# ETH_PCIE_CTRL.net
KiCad netlist of a schematic drawn in Altium Designer
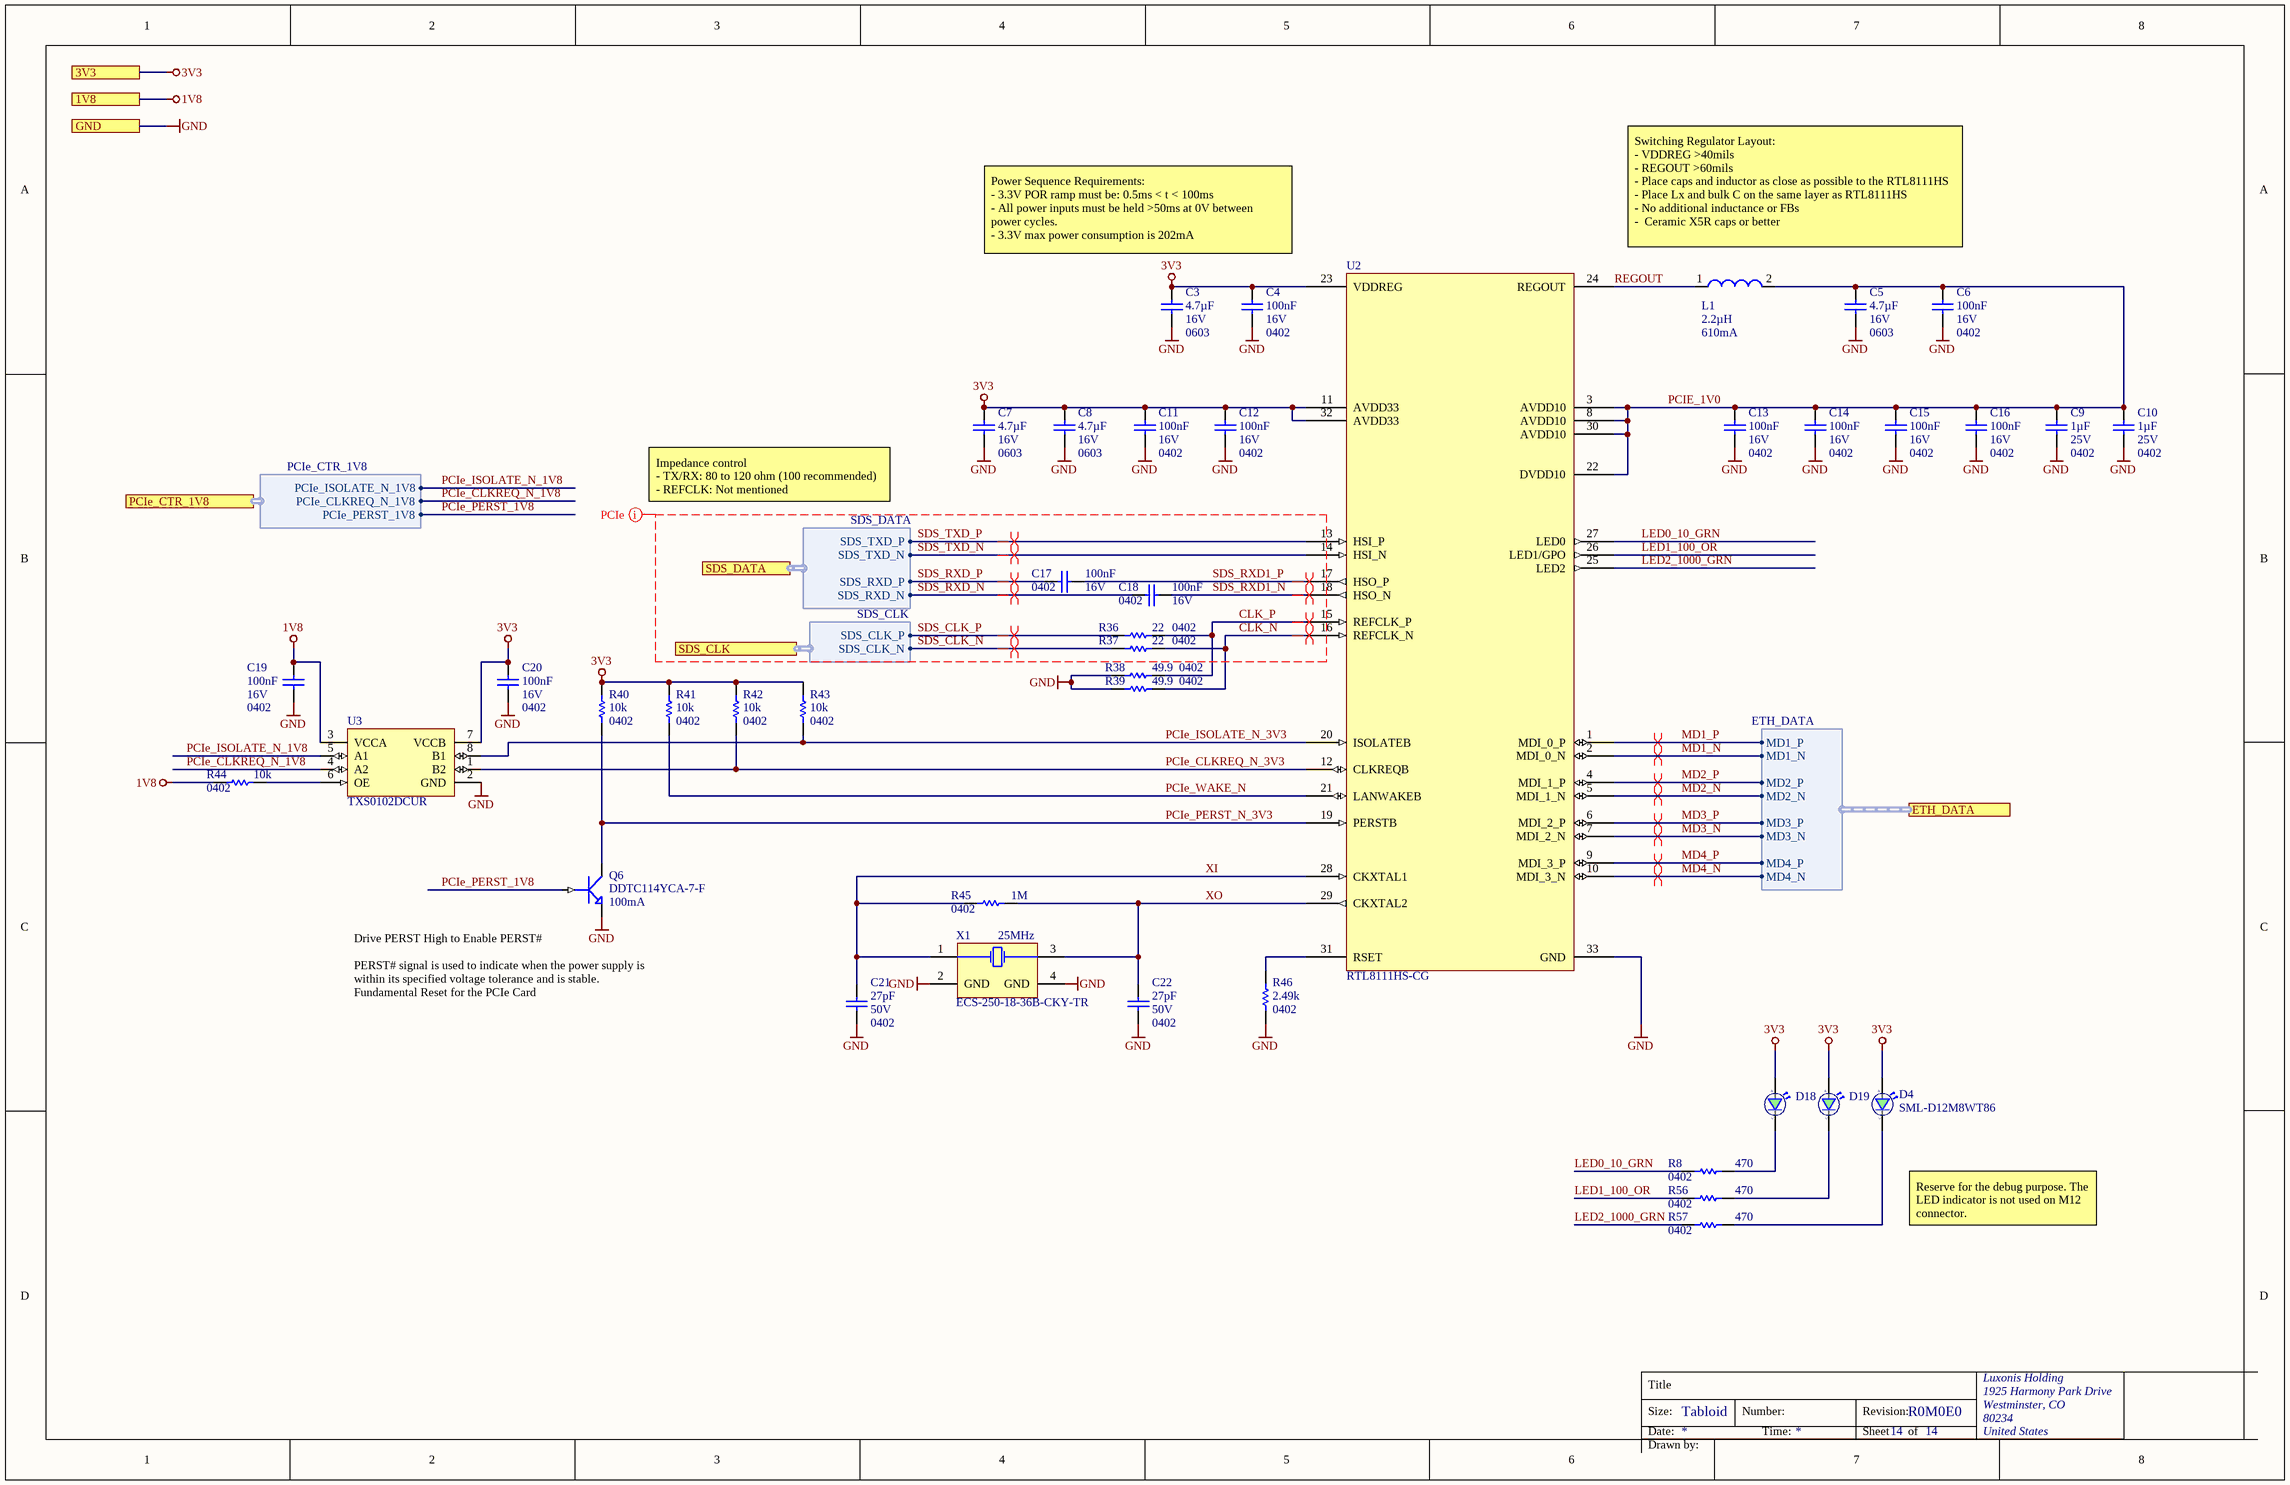
[diagram p0: ETH_PCIE_CTRL.SchDoc]

(export (version "E")
  (design (tool "Eeschema 10.0.6"))
  (components
    (comp (ref "C3")
      (value "4.7µF")
      (footprint "CAPC0603(1608)100_N")
      (description "CAP CER 4.7UF 16V X5R 0603 10%")
      (fields
        (field (name "VOLTAGE RATING") "16V")
        (field (name "CASE/PACKAGE") "0603")
        (field (name "TOLERANCE") "10%")
        (field (name "Comment") "GRM188R61C475KAAJD")
      )
      (libsource (lib "Luxonis LLC") (part "LLL153C70G474ME17E"))
    )
    (comp (ref "C4")
      (value "100nF")
      (footprint "CAPC0402(1005)60_N")
      (description "CAP CER 0.1UF 16V X7R 0402 10%")
      (fields
        (field (name "VOLTAGE RATING") "16V")
        (field (name "CASE/PACKAGE") "0402")
        (field (name "TOLERANCE") "10%")
        (field (name "Comment") "CL05B104KO5NFNC")
      )
      (libsource (lib "Luxonis LLC") (part "GRM188R61C475KAAJD"))
    )
    (comp (ref "C5")
      (value "4.7µF")
      (footprint "CAPC0603(1608)100_N")
      (description "CAP CER 4.7UF 16V X5R 0603 10%")
      (fields
        (field (name "VOLTAGE RATING") "16V")
        (field (name "CASE/PACKAGE") "0603")
        (field (name "TOLERANCE") "10%")
        (field (name "Comment") "GRM188R61C475KAAJD")
      )
      (libsource (lib "Luxonis LLC") (part "LLL153C70G474ME17E"))
    )
    (comp (ref "C6")
      (value "100nF")
      (footprint "CAPC0402(1005)60_N")
      (description "CAP CER 0.1UF 16V X7R 0402 10%")
      (fields
        (field (name "VOLTAGE RATING") "16V")
        (field (name "CASE/PACKAGE") "0402")
        (field (name "TOLERANCE") "10%")
        (field (name "Comment") "CL05B104KO5NFNC")
      )
      (libsource (lib "Luxonis LLC") (part "GRM188R61C475KAAJD"))
    )
    (comp (ref "C7")
      (value "4.7µF")
      (footprint "CAPC0603(1608)100_N")
      (description "CAP CER 4.7UF 16V X5R 0603 10%")
      (fields
        (field (name "VOLTAGE RATING") "16V")
        (field (name "CASE/PACKAGE") "0603")
        (field (name "TOLERANCE") "10%")
        (field (name "Comment") "GRM188R61C475KAAJD")
      )
      (libsource (lib "Luxonis LLC") (part "LLL153C70G474ME17E"))
    )
    (comp (ref "C8")
      (value "4.7µF")
      (footprint "CAPC0603(1608)100_N")
      (description "CAP CER 4.7UF 16V X5R 0603 10%")
      (fields
        (field (name "VOLTAGE RATING") "16V")
        (field (name "CASE/PACKAGE") "0603")
        (field (name "TOLERANCE") "10%")
        (field (name "Comment") "GRM188R61C475KAAJD")
      )
      (libsource (lib "Luxonis LLC") (part "LLL153C70G474ME17E"))
    )
    (comp (ref "C9")
      (value "1µF")
      (footprint "CAPC0402(1005)70_N")
      (description "CAP CER 1UF 25V X5R 0402 10%")
      (fields
        (field (name "VOLTAGE RATING") "25V")
        (field (name "CASE/PACKAGE") "0402")
        (field (name "TOLERANCE") "10%")
        (field (name "Comment") "GRM155R61E105KA12D")
      )
      (libsource (lib "Luxonis LLC") (part "GRM188R61C475KAAJD"))
    )
    (comp (ref "C10")
      (value "1µF")
      (footprint "CAPC0402(1005)70_N")
      (description "CAP CER 1UF 25V X5R 0402 10%")
      (fields
        (field (name "VOLTAGE RATING") "25V")
        (field (name "CASE/PACKAGE") "0402")
        (field (name "TOLERANCE") "10%")
        (field (name "Comment") "GRM155R61E105KA12D")
      )
      (libsource (lib "Luxonis LLC") (part "GRM188R61C475KAAJD"))
    )
    (comp (ref "C11")
      (value "100nF")
      (footprint "CAPC0402(1005)60_N")
      (description "CAP CER 0.1UF 16V X7R 0402 10%")
      (fields
        (field (name "VOLTAGE RATING") "16V")
        (field (name "CASE/PACKAGE") "0402")
        (field (name "TOLERANCE") "10%")
        (field (name "Comment") "CL05B104KO5NFNC")
      )
      (libsource (lib "Luxonis LLC") (part "GRM188R61C475KAAJD"))
    )
    (comp (ref "C12")
      (value "100nF")
      (footprint "CAPC0402(1005)60_N")
      (description "CAP CER 0.1UF 16V X7R 0402 10%")
      (fields
        (field (name "VOLTAGE RATING") "16V")
        (field (name "CASE/PACKAGE") "0402")
        (field (name "TOLERANCE") "10%")
        (field (name "Comment") "CL05B104KO5NFNC")
      )
      (libsource (lib "Luxonis LLC") (part "GRM188R61C475KAAJD"))
    )
    (comp (ref "C13")
      (value "100nF")
      (footprint "CAPC0402(1005)60_N")
      (description "CAP CER 0.1UF 16V X7R 0402 10%")
      (fields
        (field (name "VOLTAGE RATING") "16V")
        (field (name "CASE/PACKAGE") "0402")
        (field (name "TOLERANCE") "10%")
        (field (name "Comment") "CL05B104KO5NFNC")
      )
      (libsource (lib "Luxonis LLC") (part "GRM188R61C475KAAJD"))
    )
    (comp (ref "C14")
      (value "100nF")
      (footprint "CAPC0402(1005)60_N")
      (description "CAP CER 0.1UF 16V X7R 0402 10%")
      (fields
        (field (name "VOLTAGE RATING") "16V")
        (field (name "CASE/PACKAGE") "0402")
        (field (name "TOLERANCE") "10%")
        (field (name "Comment") "CL05B104KO5NFNC")
      )
      (libsource (lib "Luxonis LLC") (part "GRM188R61C475KAAJD"))
    )
    (comp (ref "C15")
      (value "100nF")
      (footprint "CAPC0402(1005)60_N")
      (description "CAP CER 0.1UF 16V X7R 0402 10%")
      (fields
        (field (name "VOLTAGE RATING") "16V")
        (field (name "CASE/PACKAGE") "0402")
        (field (name "TOLERANCE") "10%")
        (field (name "Comment") "CL05B104KO5NFNC")
      )
      (libsource (lib "Luxonis LLC") (part "GRM188R61C475KAAJD"))
    )
    (comp (ref "C16")
      (value "100nF")
      (footprint "CAPC0402(1005)60_N")
      (description "CAP CER 0.1UF 16V X7R 0402 10%")
      (fields
        (field (name "VOLTAGE RATING") "16V")
        (field (name "CASE/PACKAGE") "0402")
        (field (name "TOLERANCE") "10%")
        (field (name "Comment") "CL05B104KO5NFNC")
      )
      (libsource (lib "Luxonis LLC") (part "GRM188R61C475KAAJD"))
    )
    (comp (ref "C17")
      (value "100nF")
      (footprint "CAPC0402(1005)60_N")
      (description "CAP CER 0.1UF 16V X7R 0402 10%")
      (fields
        (field (name "VOLTAGE RATING") "16V")
        (field (name "CASE/PACKAGE") "0402")
        (field (name "TOLERANCE") "10%")
        (field (name "Comment") "CL05B104KO5NFNC")
      )
      (libsource (lib "Luxonis LLC") (part "GRM188R61C475KAAJD"))
    )
    (comp (ref "C18")
      (value "100nF")
      (footprint "CAPC0402(1005)60_N")
      (description "CAP CER 0.1UF 16V X7R 0402 10%")
      (fields
        (field (name "VOLTAGE RATING") "16V")
        (field (name "CASE/PACKAGE") "0402")
        (field (name "TOLERANCE") "10%")
        (field (name "Comment") "CL05B104KO5NFNC")
      )
      (libsource (lib "Luxonis LLC") (part "GRM188R61C475KAAJD"))
    )
    (comp (ref "C19")
      (value "100nF")
      (footprint "CAPC0402(1005)60_N")
      (description "CAP CER 0.1UF 16V X7R 0402 10%")
      (fields
        (field (name "VOLTAGE RATING") "16V")
        (field (name "CASE/PACKAGE") "0402")
        (field (name "TOLERANCE") "10%")
        (field (name "Comment") "CL05B104KO5NFNC")
      )
      (libsource (lib "Luxonis LLC") (part "GRM188R61C475KAAJD"))
    )
    (comp (ref "C20")
      (value "100nF")
      (footprint "CAPC0402(1005)60_N")
      (description "CAP CER 0.1UF 16V X7R 0402 10%")
      (fields
        (field (name "VOLTAGE RATING") "16V")
        (field (name "CASE/PACKAGE") "0402")
        (field (name "TOLERANCE") "10%")
        (field (name "Comment") "CL05B104KO5NFNC")
      )
      (libsource (lib "Luxonis LLC") (part "GRM188R61C475KAAJD"))
    )
    (comp (ref "C21")
      (value "27pF")
      (footprint "CAPC0402(1005)60_N")
      (description "CAP CER 27PF 50V C0G 0402 5%")
      (fields
        (field (name "VOLTAGE RATING") "50V")
        (field (name "TOLERANCE") "5%")
        (field (name "CASE/PACKAGE") "0402")
        (field (name "Comment") "C0402C270J5GACTU")
      )
      (libsource (lib "Luxonis LLC") (part "GRM188R61C475KAAJD"))
    )
    (comp (ref "C22")
      (value "27pF")
      (footprint "CAPC0402(1005)60_N")
      (description "CAP CER 27PF 50V C0G 0402 5%")
      (fields
        (field (name "VOLTAGE RATING") "50V")
        (field (name "TOLERANCE") "5%")
        (field (name "CASE/PACKAGE") "0402")
        (field (name "Comment") "C0402C270J5GACTU")
      )
      (libsource (lib "Luxonis LLC") (part "GRM188R61C475KAAJD"))
    )
    (comp (ref "D4")
      (value "SML-D12M8WT86")
      (footprint "SML_D1xx8W")
      (description "LED GREEN DIFFUSED 0603 SMD Green 572nm LED Indication - Discrete 2.2V 0603 (1608 Metric)")
      (libsource (lib "Luxonis LLC") (part "SML-D12M8WT86"))
    )
    (comp (ref "D18")
      (value "SML-D12M8WT86")
      (footprint "SML_D1xx8W")
      (description "LED GREEN DIFFUSED 0603 SMD Green 572nm LED Indication - Discrete 2.2V 0603 (1608 Metric)")
      (libsource (lib "Luxonis LLC") (part "SML-D12M8WT86"))
    )
    (comp (ref "D19")
      (value "SML-D12M8WT86")
      (footprint "SML_D1xx8W")
      (description "LED GREEN DIFFUSED 0603 SMD Green 572nm LED Indication - Discrete 2.2V 0603 (1608 Metric)")
      (libsource (lib "Luxonis LLC") (part "SML-D12M8WT86"))
    )
    (comp (ref "L1")
      (value "2.2µH")
      (footprint "LQH32NH2R2J23L")
      (description "FIXED IND 2.2UH 610MA 97MOHM SMD")
      (fields
        (field (name "TOLERANCE") "5%")
        (field (name "CURRENT RATING") "610mA")
        (field (name "Comment") "LQH32NH2R2J23L")
      )
      (libsource (lib "Luxonis LLC") (part "DFE252012P-1R0M=P2"))
    )
    (comp (ref "Q6")
      (value "DDTC114YCA-7-F")
      (footprint "DDTC114YCA-7-F-Footprint-1")
      (description "TRANS PREBIAS NPN 200MW SOT23-3")
      (fields (field (name "CONTINUOUS DRAIN CURRENT") "100mA"))
      (libsource (lib "Luxonis LLC") (part "DDTC114YCA-7-F"))
    )
    (comp (ref "R8")
      (value "470")
      (footprint "RESC0402(1005)_L")
      (description "RES SMD 470 OHM 1% 1/16W 0402")
      (fields
        (field (name "CASE/PACKAGE") "0402")
        (field (name "TOLERANCE") "1%")
        (field (name "Comment") "CRCW0402470RFKED")
      )
      (libsource (lib "Luxonis LLC") (part "Default resistor symbol"))
    )
    (comp (ref "R36")
      (value "22")
      (footprint "RESC0402(1005)_N")
      (description "RES SMD 22 OHM 1% 1/16W 0402")
      (fields
        (field (name "CASE/PACKAGE") "0402")
        (field (name "TOLERANCE") "1%")
        (field (name "Comment") "RC0402FR-0722RL")
      )
      (libsource (lib "Luxonis LLC") (part "Default resistor symbol"))
    )
    (comp (ref "R37")
      (value "22")
      (footprint "RESC0402(1005)_N")
      (description "RES SMD 22 OHM 1% 1/16W 0402")
      (fields
        (field (name "CASE/PACKAGE") "0402")
        (field (name "TOLERANCE") "1%")
        (field (name "Comment") "RC0402FR-0722RL")
      )
      (libsource (lib "Luxonis LLC") (part "Default resistor symbol"))
    )
    (comp (ref "R38")
      (value "49.9")
      (footprint "RESC0402(1005)_L")
      (description "RES SMD 49.9 OHM 1% 1/16W 0402")
      (fields
        (field (name "TOLERANCE") "1%")
        (field (name "CASE/PACKAGE") "0402")
        (field (name "Comment") "RC0402FR-0749R9L")
      )
      (libsource (lib "Luxonis LLC") (part "RC0402FR-0722RL_1"))
    )
    (comp (ref "R39")
      (value "49.9")
      (footprint "RESC0402(1005)_L")
      (description "RES SMD 49.9 OHM 1% 1/16W 0402")
      (fields
        (field (name "TOLERANCE") "1%")
        (field (name "CASE/PACKAGE") "0402")
        (field (name "Comment") "RC0402FR-0749R9L")
      )
      (libsource (lib "Luxonis LLC") (part "RC0402FR-0722RL_1"))
    )
    (comp (ref "R40")
      (value "10k")
      (footprint "RESC0402(1005)_N")
      (description "RES SMD 10K OHM 1% 1/16W 0402")
      (fields
        (field (name "CASE/PACKAGE") "0402")
        (field (name "TOLERANCE") "1%")
        (field (name "Comment") "RC0402FR-1310KL")
      )
      (libsource (lib "Luxonis LLC") (part "RC0402FR-0722RL_1"))
    )
    (comp (ref "R41")
      (value "10k")
      (footprint "RESC0402(1005)_N")
      (description "RES SMD 10K OHM 1% 1/16W 0402")
      (fields
        (field (name "CASE/PACKAGE") "0402")
        (field (name "TOLERANCE") "1%")
        (field (name "Comment") "RC0402FR-1310KL")
      )
      (libsource (lib "Luxonis LLC") (part "RC0402FR-0722RL_1"))
    )
    (comp (ref "R42")
      (value "10k")
      (footprint "RESC0402(1005)_N")
      (description "RES SMD 10K OHM 1% 1/16W 0402")
      (fields
        (field (name "CASE/PACKAGE") "0402")
        (field (name "TOLERANCE") "1%")
        (field (name "Comment") "RC0402FR-1310KL")
      )
      (libsource (lib "Luxonis LLC") (part "RC0402FR-0722RL_1"))
    )
    (comp (ref "R43")
      (value "10k")
      (footprint "RESC0402(1005)_N")
      (description "RES SMD 10K OHM 1% 1/16W 0402")
      (fields
        (field (name "CASE/PACKAGE") "0402")
        (field (name "TOLERANCE") "1%")
        (field (name "Comment") "RC0402FR-1310KL")
      )
      (libsource (lib "Luxonis LLC") (part "RC0402FR-0722RL_1"))
    )
    (comp (ref "R44")
      (value "10k")
      (footprint "RESC0402(1005)_N")
      (description "RES SMD 10K OHM 1% 1/16W 0402")
      (fields
        (field (name "CASE/PACKAGE") "0402")
        (field (name "TOLERANCE") "1%")
        (field (name "Comment") "RC0402FR-1310KL")
      )
      (libsource (lib "Luxonis LLC") (part "RC0402FR-0722RL_1"))
    )
    (comp (ref "R45")
      (value "1M")
      (footprint "RESC0402(1005)_L")
      (description "RES SMD 1M OHM 1% 1/16W 0402")
      (fields
        (field (name "CASE/PACKAGE") "0402")
        (field (name "TOLERANCE") "1%")
        (field (name "Comment") "RC0402FR-071ML")
      )
      (libsource (lib "Luxonis LLC") (part "Default resistor symbol"))
    )
    (comp (ref "R46")
      (value "2.49k")
      (footprint "RESC0402(1005)_N")
      (description "RES SMD 2.49K OHM 1% 1/16W 0402")
      (fields
        (field (name "CASE/PACKAGE") "0402")
        (field (name "TOLERANCE") "1%")
        (field (name "Comment") "RC0402FR-072K49L")
      )
      (libsource (lib "Luxonis LLC") (part "RC0402FR-0722RL_1"))
    )
    (comp (ref "R56")
      (value "470")
      (footprint "RESC0402(1005)_L")
      (description "RES SMD 470 OHM 1% 1/16W 0402")
      (fields
        (field (name "CASE/PACKAGE") "0402")
        (field (name "TOLERANCE") "1%")
        (field (name "Comment") "CRCW0402470RFKED")
      )
      (libsource (lib "Luxonis LLC") (part "Default resistor symbol"))
    )
    (comp (ref "R57")
      (value "470")
      (footprint "RESC0402(1005)_L")
      (description "RES SMD 470 OHM 1% 1/16W 0402")
      (fields
        (field (name "CASE/PACKAGE") "0402")
        (field (name "TOLERANCE") "1%")
        (field (name "Comment") "CRCW0402470RFKED")
      )
      (libsource (lib "Luxonis LLC") (part "Default resistor symbol"))
    )
    (comp (ref "U2")
      (value "RTL8111HS-CG")
      (footprint "BW2098POE:RTL8111Hx-CG")
      (description "IC ETHERNET/PCIe PHY Realtek")
      (libsource (lib "BW2098POE") (part "RTL8111HS"))
    )
    (comp (ref "U3")
      (value "TXS0102DCUR")
      (footprint "TXS0102DCUR")
      (description "TEXAS INSTRUMENTS - TXS0102DCUR - IC, TRANSLATOR, 2 BIT, BI, US-8")
      (libsource (lib "Luxonis LLC") (part "TXS0102DCUR"))
    )
    (comp (ref "X1")
      (value "ECS-250-18-36B-CKY-TR")
      (footprint "ECS-250-18-36B-CKY-TR")
      (description "CRYSTAL 25.0000MHZ 18PF SMD 25MHz ±10ppm Crystal 18pF 50 Ohms 4-SMD, No Lead")
      (fields (field (name "FREQUENCY") "25MHz"))
      (libsource (lib "Luxonis LLC") (part "ECS-250-18-36B-CKY-TR"))
    )
  )
  (nets
    (net (code "5") (name "/CLK_N") (class "Default")
      (node (ref "R37") (pin "2") (pinfunction "2_2") (pintype "passive"))
      (node (ref "R39") (pin "2") (pinfunction "2_2") (pintype "passive"))
      (node (ref "U2") (pin "16") (pinfunction "REFCLK_N_16") (pintype "input"))
    )
    (net (code "6") (name "/CLK_P") (class "Default")
      (node (ref "R36") (pin "2") (pinfunction "2_2") (pintype "passive"))
      (node (ref "R38") (pin "2") (pinfunction "2_2") (pintype "passive"))
      (node (ref "U2") (pin "15") (pinfunction "REFCLK_P_15") (pintype "input"))
    )
    (net (code "7") (name "/LED0_10_GRN") (class "Default")
      (node (ref "R8") (pin "1") (pinfunction "1_1") (pintype "passive"))
      (node (ref "U2") (pin "27") (pinfunction "LED0_27") (pintype "output"))
    )
    (net (code "8") (name "/LED1_100_OR") (class "Default")
      (node (ref "R56") (pin "1") (pinfunction "1_1") (pintype "passive"))
      (node (ref "U2") (pin "26") (pinfunction "LED1/GPO_26") (pintype "output"))
    )
    (net (code "9") (name "/LED2_1000_GRN") (class "Default")
      (node (ref "R57") (pin "1") (pinfunction "1_1") (pintype "passive"))
      (node (ref "U2") (pin "25") (pinfunction "LED2_25") (pintype "output"))
    )
    (net (code "10") (name "/MD1_N") (class "Default")
      (node (ref "U2") (pin "2") (pinfunction "MDI_0_N_2") (pintype "bidirectional"))
    )
    (net (code "11") (name "/MD1_P") (class "Default")
      (node (ref "U2") (pin "1") (pinfunction "MDI_0_P_1") (pintype "bidirectional"))
    )
    (net (code "12") (name "/MD2_N") (class "Default")
      (node (ref "U2") (pin "5") (pinfunction "MDI_1_N_5") (pintype "bidirectional"))
    )
    (net (code "13") (name "/MD2_P") (class "Default")
      (node (ref "U2") (pin "4") (pinfunction "MDI_1_P_4") (pintype "bidirectional"))
    )
    (net (code "14") (name "/MD3_N") (class "Default")
      (node (ref "U2") (pin "7") (pinfunction "MDI_2_N_7") (pintype "bidirectional"))
    )
    (net (code "15") (name "/MD3_P") (class "Default")
      (node (ref "U2") (pin "6") (pinfunction "MDI_2_P_6") (pintype "bidirectional"))
    )
    (net (code "16") (name "/MD4_N") (class "Default")
      (node (ref "U2") (pin "10") (pinfunction "MDI_3_N_10") (pintype "bidirectional"))
    )
    (net (code "17") (name "/MD4_P") (class "Default")
      (node (ref "U2") (pin "9") (pinfunction "MDI_3_P_9") (pintype "bidirectional"))
    )
    (net (code "18") (name "/PCIE_1V0") (class "Default")
      (node (ref "C10") (pin "2") (pinfunction "2_2") (pintype "passive"))
      (node (ref "C13") (pin "2") (pinfunction "2_2") (pintype "passive"))
      (node (ref "C14") (pin "2") (pinfunction "2_2") (pintype "passive"))
      (node (ref "C15") (pin "2") (pinfunction "2_2") (pintype "passive"))
      (node (ref "C16") (pin "2") (pinfunction "2_2") (pintype "passive"))
      (node (ref "C5") (pin "2") (pinfunction "2_2") (pintype "passive"))
      (node (ref "C6") (pin "2") (pinfunction "2_2") (pintype "passive"))
      (node (ref "C9") (pin "2") (pinfunction "2_2") (pintype "passive"))
      (node (ref "L1") (pin "2") (pinfunction "2_2") (pintype "passive"))
      (node (ref "U2") (pin "22") (pinfunction "DVDD10_22") (pintype "passive"))
      (node (ref "U2") (pin "3") (pinfunction "AVDD10_3") (pintype "passive"))
      (node (ref "U2") (pin "30") (pinfunction "AVDD10_30") (pintype "passive"))
      (node (ref "U2") (pin "8") (pinfunction "AVDD10_8") (pintype "passive"))
    )
    (net (code "19") (name "/PCIe_CLKREQ_N_1V8") (class "Default")
      (node (ref "U3") (pin "4") (pinfunction "A2_4") (pintype "bidirectional"))
    )
    (net (code "20") (name "/PCIe_CLKREQ_N_3V3") (class "Default")
      (node (ref "R42") (pin "1") (pinfunction "1_1") (pintype "passive"))
      (node (ref "U2") (pin "12") (pinfunction "CLKREQB_12") (pintype "bidirectional"))
      (node (ref "U3") (pin "1") (pinfunction "B2_1") (pintype "bidirectional"))
    )
    (net (code "21") (name "/PCIe_ISOLATE_N_1V8") (class "Default")
      (node (ref "U3") (pin "5") (pinfunction "A1_5") (pintype "bidirectional"))
    )
    (net (code "22") (name "/PCIe_ISOLATE_N_3V3") (class "Default")
      (node (ref "R43") (pin "1") (pinfunction "1_1") (pintype "passive"))
      (node (ref "U2") (pin "20") (pinfunction "ISOLATEB_20") (pintype "input"))
      (node (ref "U3") (pin "8") (pinfunction "B1_8") (pintype "bidirectional"))
    )
    (net (code "23") (name "/PCIe_PERST_1V8") (class "Default")
      (node (ref "Q6") (pin "1") (pinfunction "B_1") (pintype "input"))
    )
    (net (code "24") (name "/PCIe_PERST_N_3V3") (class "Default")
      (node (ref "Q6") (pin "3") (pinfunction "C_3") (pintype "passive"))
      (node (ref "R40") (pin "1") (pinfunction "1_1") (pintype "passive"))
      (node (ref "U2") (pin "19") (pinfunction "PERSTB_19") (pintype "input"))
    )
    (net (code "25") (name "/PCIe_WAKE_N") (class "Default")
      (node (ref "R41") (pin "1") (pinfunction "1_1") (pintype "passive"))
      (node (ref "U2") (pin "21") (pinfunction "LANWAKEB_21") (pintype "bidirectional"))
    )
    (net (code "26") (name "/REGOUT") (class "Default")
      (node (ref "L1") (pin "1") (pinfunction "1_1") (pintype "passive"))
      (node (ref "U2") (pin "24") (pinfunction "REGOUT_24") (pintype "passive"))
    )
    (net (code "27") (name "/SDS_CLK_N") (class "Default")
      (node (ref "R37") (pin "1") (pinfunction "1_1") (pintype "passive"))
    )
    (net (code "28") (name "/SDS_CLK_P") (class "Default")
      (node (ref "R36") (pin "1") (pinfunction "1_1") (pintype "passive"))
    )
    (net (code "29") (name "/SDS_RXD1_N") (class "Default")
      (node (ref "C18") (pin "1") (pinfunction "1_1") (pintype "passive"))
      (node (ref "U2") (pin "18") (pinfunction "HSO_N_18") (pintype "output"))
    )
    (net (code "30") (name "/SDS_RXD1_P") (class "Default")
      (node (ref "C17") (pin "1") (pinfunction "1_1") (pintype "passive"))
      (node (ref "U2") (pin "17") (pinfunction "HSO_P_17") (pintype "output"))
    )
    (net (code "31") (name "/SDS_RXD_N") (class "Default")
      (node (ref "C18") (pin "2") (pinfunction "2_2") (pintype "passive"))
    )
    (net (code "32") (name "/SDS_RXD_P") (class "Default")
      (node (ref "C17") (pin "2") (pinfunction "2_2") (pintype "passive"))
    )
    (net (code "33") (name "/SDS_TXD_N") (class "Default")
      (node (ref "U2") (pin "14") (pinfunction "HSI_N_14") (pintype "input"))
    )
    (net (code "34") (name "/SDS_TXD_P") (class "Default")
      (node (ref "U2") (pin "13") (pinfunction "HSI_P_13") (pintype "input"))
    )
    (net (code "35") (name "/XI") (class "Default")
      (node (ref "C21") (pin "2") (pinfunction "2_2") (pintype "passive"))
      (node (ref "R45") (pin "1") (pinfunction "1_1") (pintype "passive"))
      (node (ref "U2") (pin "28") (pinfunction "CKXTAL1_28") (pintype "input"))
      (node (ref "X1") (pin "1") (pinfunction "X1_1") (pintype "passive"))
    )
    (net (code "36") (name "/XO") (class "Default")
      (node (ref "C22") (pin "2") (pinfunction "2_2") (pintype "passive"))
      (node (ref "R45") (pin "2") (pinfunction "2_2") (pintype "passive"))
      (node (ref "U2") (pin "29") (pinfunction "CKXTAL2_29") (pintype "output"))
      (node (ref "X1") (pin "3") (pinfunction "X2_3") (pintype "passive"))
    )
    (net (code "41") (name "1V8") (class "Default")
      (node (ref "C19") (pin "2") (pinfunction "2_2") (pintype "passive"))
      (node (ref "R44") (pin "1") (pinfunction "1_1") (pintype "passive"))
      (node (ref "U3") (pin "3") (pinfunction "VCCA_3") (pintype "power_in"))
    )
    (net (code "42") (name "3V3") (class "Default")
      (node (ref "C11") (pin "2") (pinfunction "2_2") (pintype "passive"))
      (node (ref "C12") (pin "2") (pinfunction "2_2") (pintype "passive"))
      (node (ref "C20") (pin "2") (pinfunction "2_2") (pintype "passive"))
      (node (ref "C3") (pin "2") (pinfunction "2_2") (pintype "passive"))
      (node (ref "C4") (pin "2") (pinfunction "2_2") (pintype "passive"))
      (node (ref "C7") (pin "2") (pinfunction "2_2") (pintype "passive"))
      (node (ref "C8") (pin "2") (pinfunction "2_2") (pintype "passive"))
      (node (ref "D18") (pin "2") (pinfunction "A_2") (pintype "passive"))
      (node (ref "D19") (pin "2") (pinfunction "A_2") (pintype "passive"))
      (node (ref "D4") (pin "2") (pinfunction "A_2") (pintype "passive"))
      (node (ref "R40") (pin "2") (pinfunction "2_2") (pintype "passive"))
      (node (ref "R41") (pin "2") (pinfunction "2_2") (pintype "passive"))
      (node (ref "R42") (pin "2") (pinfunction "2_2") (pintype "passive"))
      (node (ref "R43") (pin "2") (pinfunction "2_2") (pintype "passive"))
      (node (ref "U2") (pin "11") (pinfunction "AVDD33_11") (pintype "passive"))
      (node (ref "U2") (pin "23") (pinfunction "VDDREG_23") (pintype "passive"))
      (node (ref "U2") (pin "32") (pinfunction "AVDD33_32") (pintype "passive"))
      (node (ref "U3") (pin "7") (pinfunction "VCCB_7") (pintype "power_in"))
    )
    (net (code "43") (name "GND") (class "Default")
      (node (ref "C10") (pin "1") (pinfunction "1_1") (pintype "passive"))
      (node (ref "C11") (pin "1") (pinfunction "1_1") (pintype "passive"))
      (node (ref "C12") (pin "1") (pinfunction "1_1") (pintype "passive"))
      (node (ref "C13") (pin "1") (pinfunction "1_1") (pintype "passive"))
      (node (ref "C14") (pin "1") (pinfunction "1_1") (pintype "passive"))
      (node (ref "C15") (pin "1") (pinfunction "1_1") (pintype "passive"))
      (node (ref "C16") (pin "1") (pinfunction "1_1") (pintype "passive"))
      (node (ref "C19") (pin "1") (pinfunction "1_1") (pintype "passive"))
      (node (ref "C20") (pin "1") (pinfunction "1_1") (pintype "passive"))
      (node (ref "C21") (pin "1") (pinfunction "1_1") (pintype "passive"))
      (node (ref "C22") (pin "1") (pinfunction "1_1") (pintype "passive"))
      (node (ref "C3") (pin "1") (pinfunction "1_1") (pintype "passive"))
      (node (ref "C4") (pin "1") (pinfunction "1_1") (pintype "passive"))
      (node (ref "C5") (pin "1") (pinfunction "1_1") (pintype "passive"))
      (node (ref "C6") (pin "1") (pinfunction "1_1") (pintype "passive"))
      (node (ref "C7") (pin "1") (pinfunction "1_1") (pintype "passive"))
      (node (ref "C8") (pin "1") (pinfunction "1_1") (pintype "passive"))
      (node (ref "C9") (pin "1") (pinfunction "1_1") (pintype "passive"))
      (node (ref "Q6") (pin "2") (pinfunction "E_2") (pintype "passive"))
      (node (ref "R38") (pin "1") (pinfunction "1_1") (pintype "passive"))
      (node (ref "R39") (pin "1") (pinfunction "1_1") (pintype "passive"))
      (node (ref "R46") (pin "1") (pinfunction "1_1") (pintype "passive"))
      (node (ref "U2") (pin "33") (pinfunction "GND_33") (pintype "passive"))
      (node (ref "U3") (pin "2") (pinfunction "GND_2") (pintype "power_in"))
      (node (ref "X1") (pin "2") (pinfunction "GND_2") (pintype "power_in"))
      (node (ref "X1") (pin "4") (pinfunction "GND_4") (pintype "power_in"))
    )
    (net (code "44") (name "Net-(D4-C)") (class "Default")
      (node (ref "D4") (pin "1") (pinfunction "C_1") (pintype "passive"))
      (node (ref "R57") (pin "2") (pinfunction "2_2") (pintype "passive"))
    )
    (net (code "45") (name "Net-(D18-C)") (class "Default")
      (node (ref "D18") (pin "1") (pinfunction "C_1") (pintype "passive"))
      (node (ref "R8") (pin "2") (pinfunction "2_2") (pintype "passive"))
    )
    (net (code "46") (name "Net-(D19-C)") (class "Default")
      (node (ref "D19") (pin "1") (pinfunction "C_1") (pintype "passive"))
      (node (ref "R56") (pin "2") (pinfunction "2_2") (pintype "passive"))
    )
    (net (code "47") (name "Net-(U2-RSET)") (class "Default")
      (node (ref "R46") (pin "2") (pinfunction "2_2") (pintype "passive"))
      (node (ref "U2") (pin "31") (pinfunction "RSET_31") (pintype "passive"))
    )
    (net (code "48") (name "Net-(U3-OE)") (class "Default")
      (node (ref "R44") (pin "2") (pinfunction "2_2") (pintype "passive"))
      (node (ref "U3") (pin "6") (pinfunction "OE_6") (pintype "input"))
    )
  )
)
